# 12V_switching.net
KiCad netlist of a schematic drawn in EAGLE
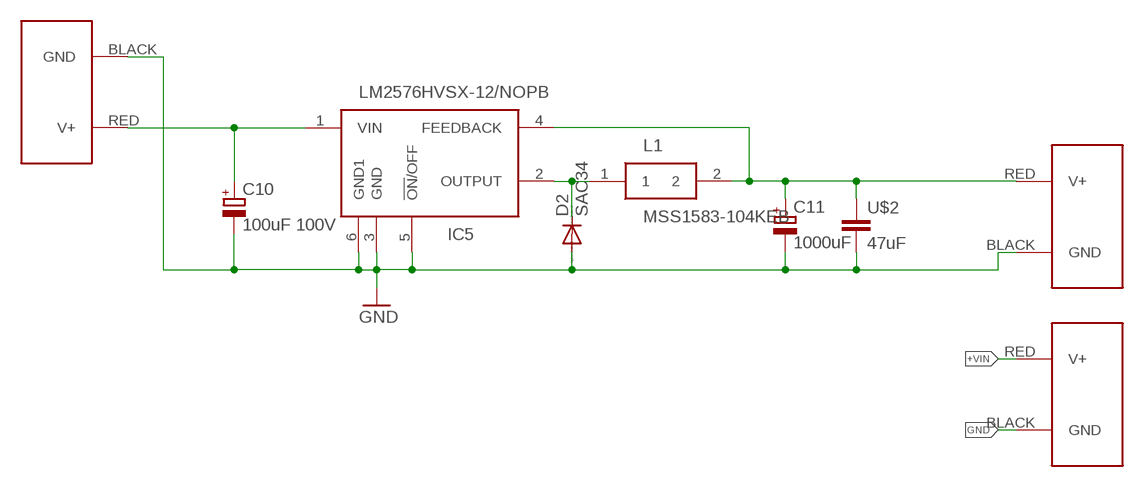
[diagram p0: schematic, sheet 1]

(export (version "E")
  (design (tool "Eeschema 10.0.6"))
  (components
    (comp (ref "C10")
      (value "100uF 100V")
      (footprint "eagle-import:UD-10X10_NICHICON")
      (libsource (lib "eagle-import") (part "CPOL-EU"))
    )
    (comp (ref "C11")
      (value "1000uF")
      (footprint "eagle-import:UD-10X10_NICHICON")
      (libsource (lib "eagle-import") (part "CPOL-EU"))
    )
    (comp (ref "D2")
      (value "SAC34")
      (footprint "eagle-import:DO-214AC")
      (libsource (lib "eagle-import") (part "DIODE-DO-214AC"))
    )
    (comp (ref "IC5")
      (value "LM2576HVSX-12/NOPB")
      (footprint "eagle-import:TO263-5")
      (fields
        (field (name "MANUFACTURER_PART_NUMBER") "LM2576D2TR4-012G ")
        (field (name "MOUSER_PART_NUMBER") "863-LM2576D2TR4-012G")
        (field (name "MOUSER_PART_NUMBER_1") " LM2576HVSX-12/NOPB")
        (field (name "MPN") " LM2576HVSX-12/NOPB")
      )
      (libsource (lib "eagle-import") (part "LM2576D2TR4-012G"))
    )
    (comp (ref "J1")
      (value "POWERPOLE_POWER45A")
      (footprint "eagle-import:POWERPOLE_PAIR_45A")
      (libsource (lib "eagle-import") (part "POWERPOLE_POWER45A"))
    )
    (comp (ref "J2")
      (value "POWERPOLE_POWER45A")
      (footprint "eagle-import:POWERPOLE_PAIR_45A")
      (libsource (lib "eagle-import") (part "POWERPOLE_POWER45A"))
    )
    (comp (ref "J3")
      (value "POWERPOLE_POWER45A")
      (footprint "eagle-import:POWERPOLE_PAIR_45A")
      (libsource (lib "eagle-import") (part "POWERPOLE_POWER45A"))
    )
    (comp (ref "L1")
      (value "MSS1583-104KEB")
      (footprint "eagle-import:INDPM150150X860N")
      (fields (field (name "MOUSER_PART_NUMBER") "994-MSS1583-104KEB"))
      (libsource (lib "eagle-import") (part "MSS1583-104KEB"))
    )
    (comp (ref "U$2")
      (value "47uF")
      (footprint "eagle-import:C1206")
      (libsource (lib "eagle-import") (part "C-EU'1206'"))
    )
  )
  (nets
    (net (code "1") (name "+VIN") (class "Default")
      (node (ref "C10") (pin "+") (pinfunction "+_+") (pintype "passive"))
      (node (ref "IC5") (pin "1") (pinfunction "VIN_1") (pintype "bidirectional"))
      (node (ref "J1") (pin "RED") (pinfunction "V+_RED") (pintype "power_in"))
      (node (ref "J3") (pin "RED") (pinfunction "V+_RED") (pintype "power_in"))
    )
    (net (code "2") (name "GND") (class "Default")
      (node (ref "C10") (pin "-") (pinfunction "-_-") (pintype "passive"))
      (node (ref "C11") (pin "-") (pinfunction "-_-") (pintype "passive"))
      (node (ref "D2") (pin "A") (pinfunction "A_A") (pintype "passive"))
      (node (ref "IC5") (pin "3") (pinfunction "GND_3") (pintype "bidirectional"))
      (node (ref "IC5") (pin "5") (pinfunction "~{ON}/OFF_5") (pintype "bidirectional"))
      (node (ref "IC5") (pin "6") (pinfunction "GND1_6") (pintype "bidirectional"))
      (node (ref "J1") (pin "BLACK") (pinfunction "GND_BLACK") (pintype "power_in"))
      (node (ref "J2") (pin "BLACK") (pinfunction "GND_BLACK") (pintype "power_in"))
      (node (ref "J3") (pin "BLACK") (pinfunction "GND_BLACK") (pintype "power_in"))
      (node (ref "U$2") (pin "2") (pinfunction "2_2") (pintype "passive"))
    )
    (net (code "3") (name "Net-(IC5-FEEDBACK)") (class "Default")
      (node (ref "C11") (pin "+") (pinfunction "+_+") (pintype "passive"))
      (node (ref "IC5") (pin "4") (pinfunction "FEEDBACK_4") (pintype "bidirectional"))
      (node (ref "J2") (pin "RED") (pinfunction "V+_RED") (pintype "power_in"))
      (node (ref "L1") (pin "2") (pinfunction "2_2") (pintype "bidirectional"))
      (node (ref "U$2") (pin "1") (pinfunction "1_1") (pintype "passive"))
    )
    (net (code "4") (name "Net-(IC5-OUTPUT)") (class "Default")
      (node (ref "D2") (pin "C") (pinfunction "C_C") (pintype "passive"))
      (node (ref "IC5") (pin "2") (pinfunction "OUTPUT_2") (pintype "bidirectional"))
      (node (ref "L1") (pin "1") (pinfunction "1_1") (pintype "bidirectional"))
    )
  )
)
